# 1-Schematic_Lora.net
KiCad netlist of a schematic drawn in EasyEDA
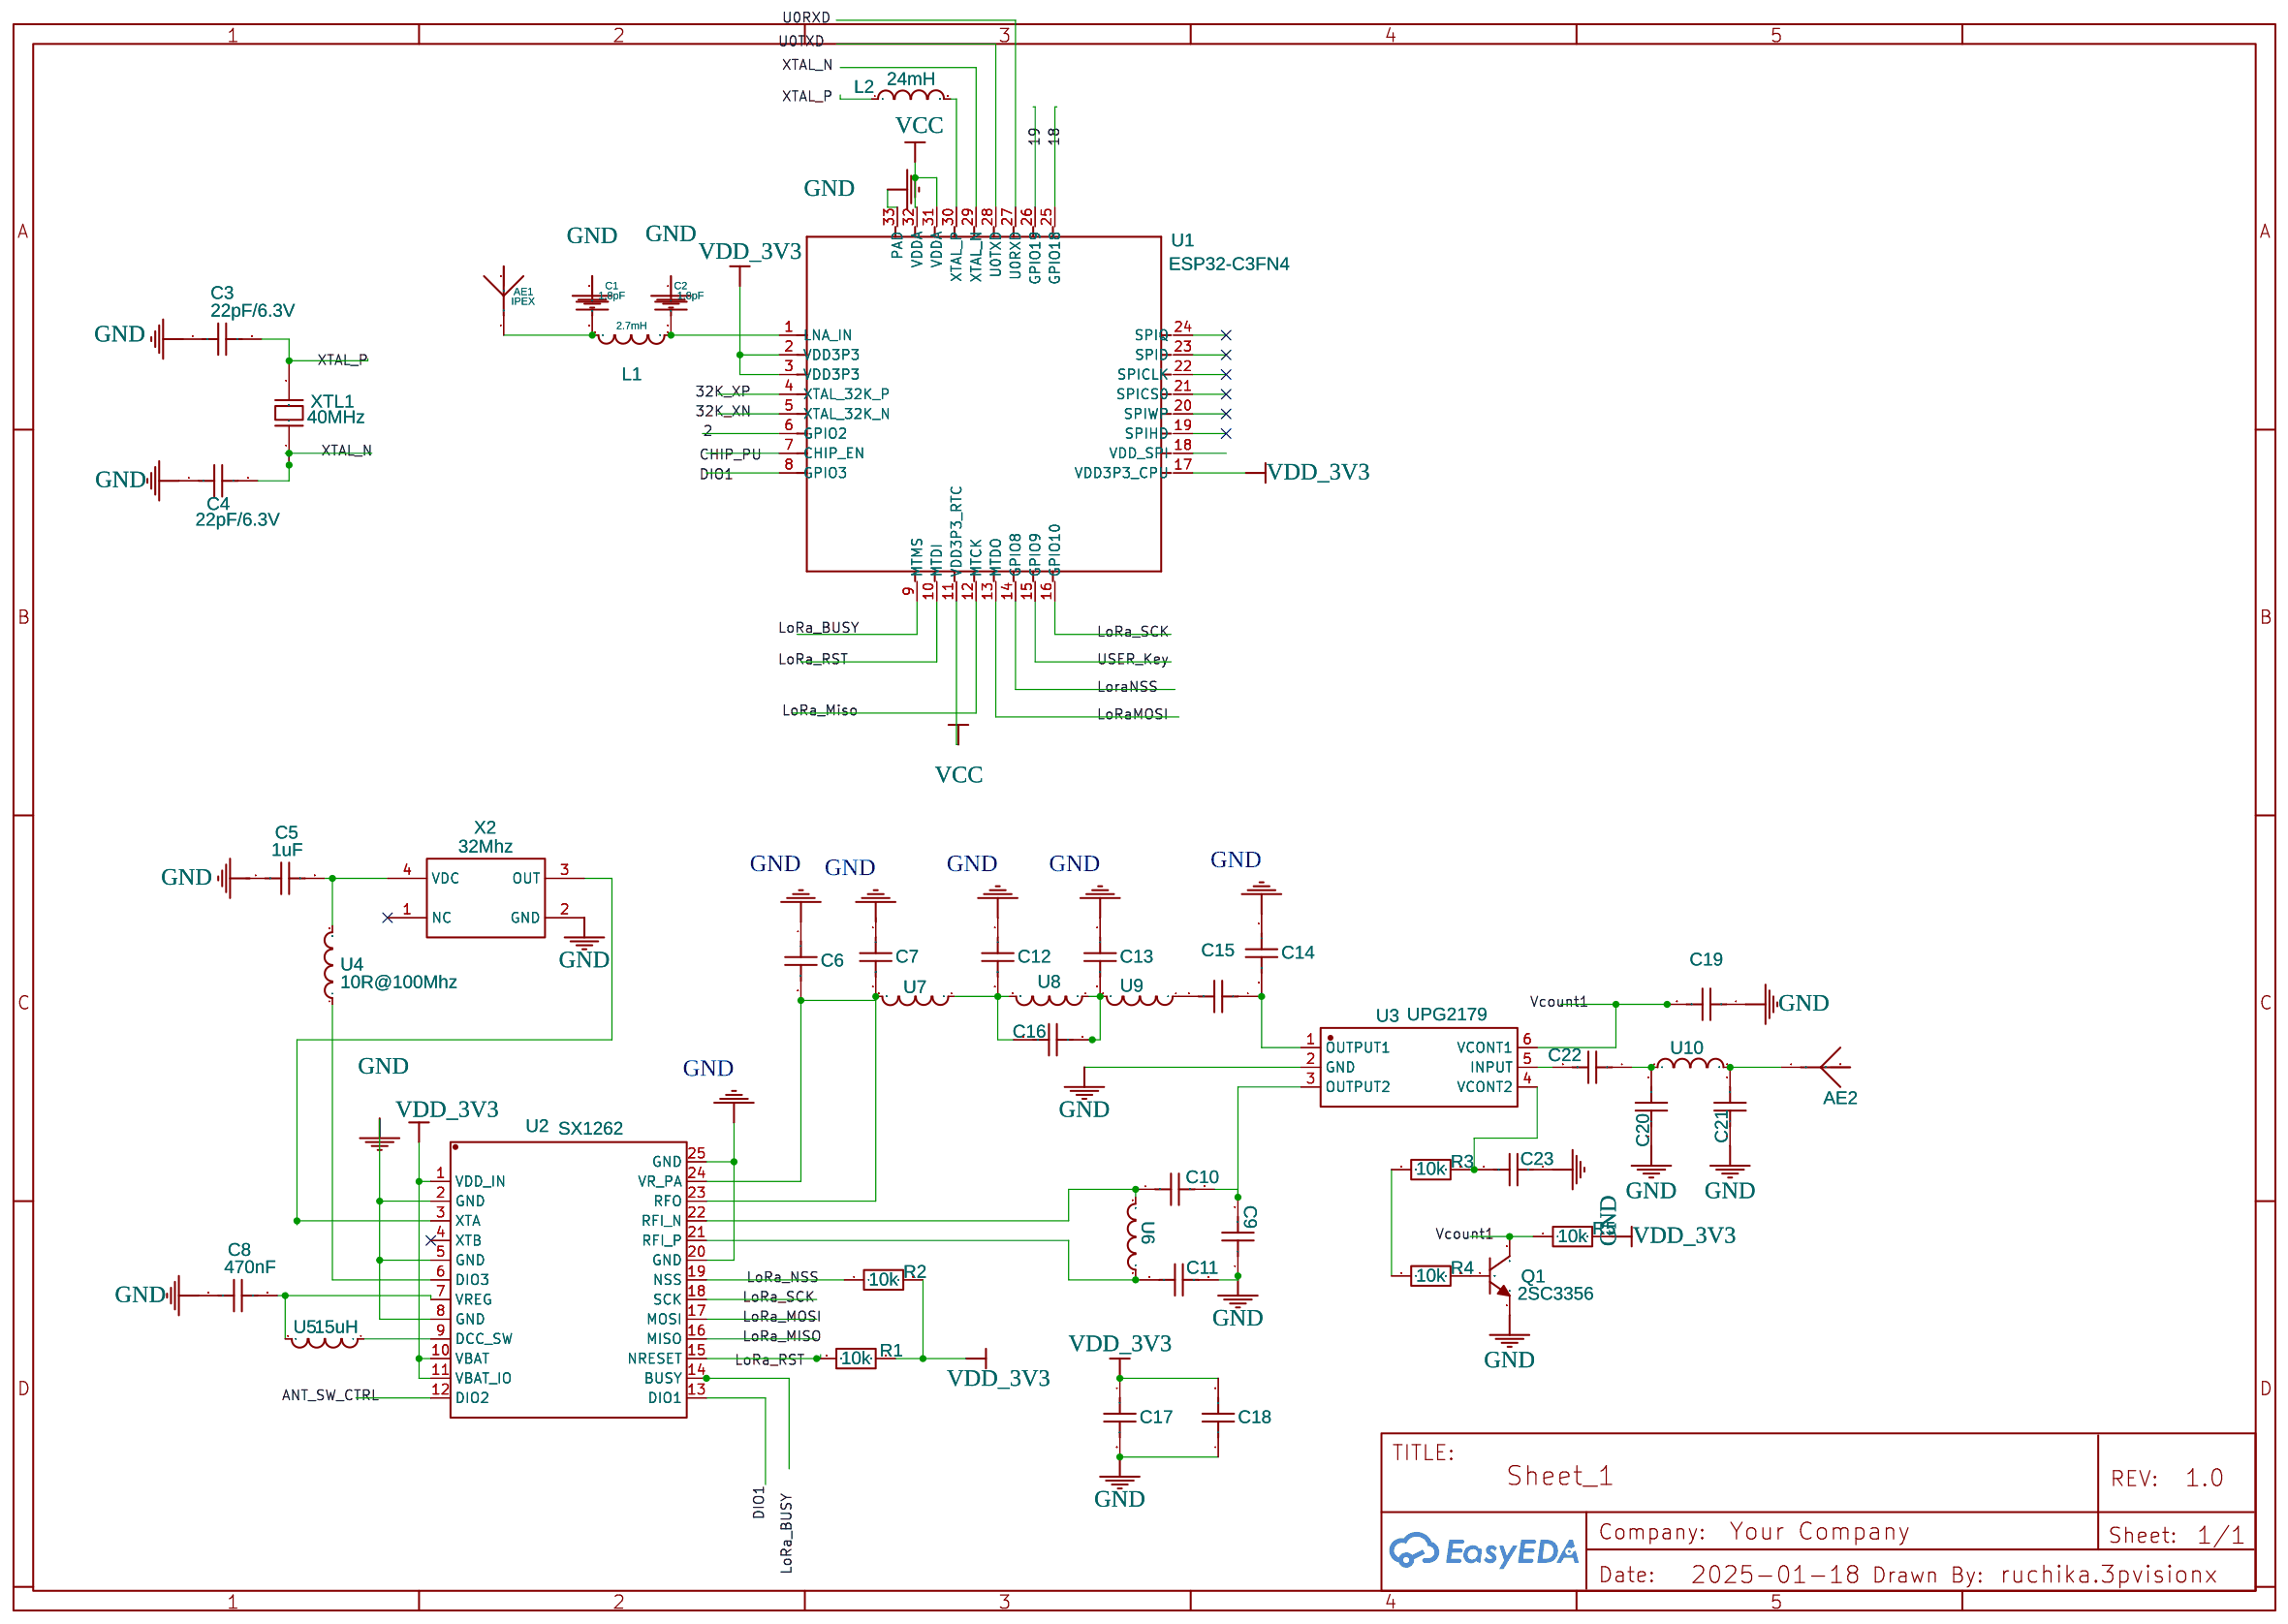
[diagram p0: schematic sheet]

(export (version "E")
  (design (tool "Eeschema 10.0.6"))
  (components
    (comp (ref "AE1")
      (value "IPEX")
      (fields
        (field (name "Manufacturer Part") "2450AT18A100E")
        (field (name "Manufacturer") "JOHANSON(约翰逊)")
      )
      (libsource (lib "") (part "2450AT18A100E"))
    )
    (comp (ref "AE2")
      (value "2450AT18A100E")
      (fields (field (name "Manufacturer") "JOHANSON(约翰逊)"))
      (libsource (lib "") (part "2450AT18A100E_1"))
    )
    (comp (ref "C1")
      (value "1.8pF")
      (fields
        (field (name "Manufacturer Part") "GJM1555C1H1R8BB01D")
        (field (name "Manufacturer") "muRata(村田)")
      )
      (libsource (lib "") (part "GJM1555C1H1R8BB01D"))
    )
    (comp (ref "C2")
      (value "1.8pF")
      (fields
        (field (name "Manufacturer Part") "GJM1555C1H1R8BB01D")
        (field (name "Manufacturer") "muRata(村田)")
      )
      (libsource (lib "") (part "GJM1555C1H1R8BB01D"))
    )
    (comp (ref "C3")
      (value "22pF/6.3V")
      (fields (field (name "Manufacturer Part") "22pF/6.3V(10%)-0402"))
      (libsource (lib "") (part "22PF/6.3V(10%)-0402"))
    )
    (comp (ref "C4")
      (value "22pF/6.3V")
      (fields (field (name "Manufacturer Part") "22pF/6.3V(10%)-0402"))
      (libsource (lib "") (part "22PF/6.3V(10%)-0402"))
    )
    (comp (ref "C5")
      (value "1uF")
      (fields
        (field (name "Manufacturer Part") "1uf/250V/CBBCapacitor")
        (field (name "Manufacturer") "ReliaPro")
      )
      (libsource (lib "") (part "1uf/250V/CBBCapacitor_2"))
    )
    (comp (ref "C6")
      (value "1uF")
      (fields
        (field (name "Manufacturer Part") "1uf/250V/CBBCapacitor")
        (field (name "Manufacturer") "ReliaPro")
      )
      (libsource (lib "") (part "1uf/250V/CBBCapacitor_1"))
    )
    (comp (ref "C7")
      (value "1uF")
      (fields
        (field (name "Manufacturer Part") "1uf/250V/CBBCapacitor")
        (field (name "Manufacturer") "ReliaPro")
      )
      (libsource (lib "") (part "1uf/250V/CBBCapacitor_1"))
    )
    (comp (ref "C8")
      (value "470nF")
      (fields
        (field (name "Manufacturer Part") "1uf/250V/CBBCapacitor")
        (field (name "Manufacturer") "ReliaPro")
      )
      (libsource (lib "") (part "1uf/250V/CBBCapacitor_2"))
    )
    (comp (ref "C9")
      (value "1uF")
      (fields
        (field (name "Manufacturer Part") "1uf/250V/CBBCapacitor")
        (field (name "Manufacturer") "ReliaPro")
      )
      (libsource (lib "") (part "1uf/250V/CBBCapacitor"))
    )
    (comp (ref "C10")
      (value "1uF")
      (fields
        (field (name "Manufacturer Part") "1uf/250V/CBBCapacitor")
        (field (name "Manufacturer") "ReliaPro")
      )
      (libsource (lib "") (part "1uf/250V/CBBCapacitor_2"))
    )
    (comp (ref "C11")
      (value "1uF")
      (fields
        (field (name "Manufacturer Part") "1uf/250V/CBBCapacitor")
        (field (name "Manufacturer") "ReliaPro")
      )
      (libsource (lib "") (part "1uf/250V/CBBCapacitor_2"))
    )
    (comp (ref "C12")
      (value "1uF")
      (fields
        (field (name "Manufacturer Part") "1uf/250V/CBBCapacitor")
        (field (name "Manufacturer") "ReliaPro")
      )
      (libsource (lib "") (part "1uf/250V/CBBCapacitor_1"))
    )
    (comp (ref "C13")
      (value "1uF")
      (fields
        (field (name "Manufacturer Part") "1uf/250V/CBBCapacitor")
        (field (name "Manufacturer") "ReliaPro")
      )
      (libsource (lib "") (part "1uf/250V/CBBCapacitor_1"))
    )
    (comp (ref "C14")
      (value "1uF")
      (fields
        (field (name "Manufacturer Part") "1uf/250V/CBBCapacitor")
        (field (name "Manufacturer") "ReliaPro")
      )
      (libsource (lib "") (part "1uf/250V/CBBCapacitor_1"))
    )
    (comp (ref "C15")
      (value "1uF")
      (fields
        (field (name "Manufacturer Part") "1uf/250V/CBBCapacitor")
        (field (name "Manufacturer") "ReliaPro")
      )
      (libsource (lib "") (part "1uf/250V/CBBCapacitor_3"))
    )
    (comp (ref "C16")
      (value "1uF")
      (fields
        (field (name "Manufacturer Part") "1uf/250V/CBBCapacitor")
        (field (name "Manufacturer") "ReliaPro")
      )
      (libsource (lib "") (part "1uf/250V/CBBCapacitor_3"))
    )
    (comp (ref "C17")
      (value "1uF")
      (fields
        (field (name "Manufacturer Part") "1uf/250V/CBBCapacitor")
        (field (name "Manufacturer") "ReliaPro")
      )
      (libsource (lib "") (part "1uf/250V/CBBCapacitor_1"))
    )
    (comp (ref "C18")
      (value "1uF")
      (fields
        (field (name "Manufacturer Part") "1uf/250V/CBBCapacitor")
        (field (name "Manufacturer") "ReliaPro")
      )
      (libsource (lib "") (part "1uf/250V/CBBCapacitor"))
    )
    (comp (ref "C19")
      (value "1uF")
      (fields
        (field (name "Manufacturer Part") "1uf/250V/CBBCapacitor")
        (field (name "Manufacturer") "ReliaPro")
      )
      (libsource (lib "") (part "1uf/250V/CBBCapacitor_3"))
    )
    (comp (ref "C20")
      (value "1uF")
      (fields
        (field (name "Manufacturer Part") "1uf/250V/CBBCapacitor")
        (field (name "Manufacturer") "ReliaPro")
      )
      (libsource (lib "") (part "1uf/250V/CBBCapacitor"))
    )
    (comp (ref "C21")
      (value "1uF")
      (fields
        (field (name "Manufacturer Part") "1uf/250V/CBBCapacitor")
        (field (name "Manufacturer") "ReliaPro")
      )
      (libsource (lib "") (part "1uf/250V/CBBCapacitor"))
    )
    (comp (ref "C22")
      (value "1uF")
      (fields
        (field (name "Manufacturer Part") "1uf/250V/CBBCapacitor")
        (field (name "Manufacturer") "ReliaPro")
      )
      (libsource (lib "") (part "1uf/250V/CBBCapacitor_3"))
    )
    (comp (ref "C23")
      (value "1uF")
      (fields
        (field (name "Manufacturer Part") "1uf/250V/CBBCapacitor")
        (field (name "Manufacturer") "ReliaPro")
      )
      (libsource (lib "") (part "1uf/250V/CBBCapacitor_3"))
    )
    (comp (ref "L1") (value "2.7mH") (libsource (lib "") (part "2.7mH sb3m")))
    (comp (ref "L2")
      (value "24mH")
      (fields (field (name "Manufacturer") "ML"))
      (libsource (lib "") (part "Inductor TH"))
    )
    (comp (ref "Q1")
      (value "2SC3356")
      (fields (field (name "Manufacturer") "FOSAN(富信)"))
      (libsource (lib "") (part "2SC3356_C5119709"))
    )
    (comp (ref "R1")
      (value "10k")
      (fields (field (name "Manufacturer Part") "贴片电阻ChipResistors"))
      (libsource (lib "") (part "贴片电阻CHIPRESISTORS"))
    )
    (comp (ref "R2")
      (value "10k")
      (fields (field (name "Manufacturer Part") "贴片电阻ChipResistors"))
      (libsource (lib "") (part "贴片电阻CHIPRESISTORS"))
    )
    (comp (ref "R3")
      (value "10k")
      (fields (field (name "Manufacturer Part") "贴片电阻ChipResistors"))
      (libsource (lib "") (part "贴片电阻CHIPRESISTORS"))
    )
    (comp (ref "R4")
      (value "10k")
      (fields (field (name "Manufacturer Part") "贴片电阻ChipResistors"))
      (libsource (lib "") (part "贴片电阻CHIPRESISTORS"))
    )
    (comp (ref "R5")
      (value "10k")
      (fields (field (name "Manufacturer Part") "贴片电阻ChipResistors"))
      (libsource (lib "") (part "贴片电阻CHIPRESISTORS"))
    )
    (comp (ref "U1") (value "ESP32-C3FN4") (libsource (lib "") (part "ESP32-C3FN4")))
    (comp (ref "U2")
      (value "SX1262")
      (fields (field (name "Manufacturer Part") "SX1262IMLTRT") (field (name "Manufacturer") "SEMTECH"))
      (libsource (lib "") (part "SX1262IMLTRT"))
    )
    (comp (ref "U3")
      (value "UPG2179")
      (fields
        (field (name "Manufacturer Part") "UPG2179TB-E4-A")
        (field (name "Manufacturer") "RENESAS(瑞萨)/IDT")
      )
      (libsource (lib "") (part "UPG2179TB-E4-A"))
    )
    (comp (ref "U4")
      (value "10R@100Mhz")
      (fields (field (name "Manufacturer Part") "10uH-INDUCTOR-0603"))
      (libsource (lib "") (part "10UH-INDUCTOR-0603_2"))
    )
    (comp (ref "U5")
      (value "15uH")
      (fields (field (name "Manufacturer Part") "10uH-INDUCTOR-0603"))
      (libsource (lib "") (part "10UH-INDUCTOR-0603_1"))
    )
    (comp (ref "U6")
      (value "15uH")
      (fields (field (name "Manufacturer Part") "10uH-INDUCTOR-0603"))
      (libsource (lib "") (part "10UH-INDUCTOR-0603_3"))
    )
    (comp (ref "U7")
      (value "15uH")
      (fields (field (name "Manufacturer Part") "10uH-INDUCTOR-0603"))
      (libsource (lib "") (part "10UH-INDUCTOR-0603"))
    )
    (comp (ref "U8")
      (value "15uH")
      (fields (field (name "Manufacturer Part") "10uH-INDUCTOR-0603"))
      (libsource (lib "") (part "10UH-INDUCTOR-0603"))
    )
    (comp (ref "U9")
      (value "15uH")
      (fields (field (name "Manufacturer Part") "10uH-INDUCTOR-0603"))
      (libsource (lib "") (part "10UH-INDUCTOR-0603_4"))
    )
    (comp (ref "U10")
      (value "15uH")
      (fields (field (name "Manufacturer Part") "10uH-INDUCTOR-0603"))
      (libsource (lib "") (part "10UH-INDUCTOR-0603_5"))
    )
    (comp (ref "X2")
      (value "32Mhz")
      (fields (field (name "Manufacturer") "YIC"))
      (libsource (lib "") (part "OSC40M-3.3/S5"))
    )
    (comp (ref "XTL1")
      (value "40MHz")
      (fields (field (name "Manufacturer Part") "NTPL INSIDE"))
      (libsource (lib "") (part "XTL - 16MHZ"))
    )
  )
  (nets
    (net (code "1") (name "/2") (class "Default")
      (node (ref "U1") (pin "6") (pinfunction "GPIO2_6") (pintype "unspecified"))
    )
    (net (code "9") (name "/LoRaMOSI") (class "Default")
      (node (ref "U1") (pin "13") (pinfunction "MTDO_13") (pintype "unspecified"))
    )
    (net (code "11") (name "/LoRa_MISO") (class "Default")
      (node (ref "U2") (pin "16") (pinfunction "MISO_16") (pintype "unspecified"))
    )
    (net (code "12") (name "/LoRa_MOSI") (class "Default")
      (node (ref "U2") (pin "17") (pinfunction "MOSI_17") (pintype "unspecified"))
    )
    (net (code "14") (name "/LoRa_NSS") (class "Default")
      (node (ref "R2") (pin "1") (pinfunction "1_1") (pintype "unspecified"))
      (node (ref "U2") (pin "19") (pinfunction "NSS_19") (pintype "unspecified"))
    )
    (net (code "16") (name "/LoRa_SCK") (class "Default")
      (node (ref "U1") (pin "16") (pinfunction "GPIO10_16") (pintype "unspecified"))
      (node (ref "U2") (pin "18") (pinfunction "SCK_18") (pintype "unspecified"))
    )
    (net (code "17") (name "/LoraNSS") (class "Default")
      (node (ref "U1") (pin "14") (pinfunction "GPIO8_14") (pintype "unspecified"))
    )
    (net (code "20") (name "/USER_Key") (class "Default")
      (node (ref "U1") (pin "15") (pinfunction "GPIO9_15") (pintype "unspecified"))
    )
    (net (code "22") (name "/XTAL_N") (class "Default")
      (node (ref "C4") (pin "2") (pinfunction "2_2") (pintype "unspecified"))
      (node (ref "XTL1") (pin "1") (pinfunction "1_1") (pintype "unspecified"))
    )
    (net (code "24") (name "GND") (class "Default")
      (node (ref "C1") (pin "1") (pinfunction "1_1") (pintype "input"))
      (node (ref "C11") (pin "2") (pinfunction "2_2") (pintype "unspecified"))
      (node (ref "C12") (pin "1") (pinfunction "1_1") (pintype "unspecified"))
      (node (ref "C13") (pin "1") (pinfunction "1_1") (pintype "unspecified"))
      (node (ref "C14") (pin "1") (pinfunction "1_1") (pintype "unspecified"))
      (node (ref "C17") (pin "2") (pinfunction "2_2") (pintype "unspecified"))
      (node (ref "C18") (pin "1") (pinfunction "1_1") (pintype "unspecified"))
      (node (ref "C19") (pin "1") (pinfunction "1_1") (pintype "unspecified"))
      (node (ref "C2") (pin "1") (pinfunction "1_1") (pintype "input"))
      (node (ref "C20") (pin "1") (pinfunction "1_1") (pintype "unspecified"))
      (node (ref "C21") (pin "1") (pinfunction "1_1") (pintype "unspecified"))
      (node (ref "C23") (pin "1") (pinfunction "1_1") (pintype "unspecified"))
      (node (ref "C3") (pin "1") (pinfunction "1_1") (pintype "unspecified"))
      (node (ref "C4") (pin "1") (pinfunction "1_1") (pintype "unspecified"))
      (node (ref "C6") (pin "1") (pinfunction "1_1") (pintype "unspecified"))
      (node (ref "C8") (pin "1") (pinfunction "1_1") (pintype "unspecified"))
      (node (ref "C9") (pin "1") (pinfunction "1_1") (pintype "unspecified"))
      (node (ref "Q1") (pin "1") (pinfunction "E_1") (pintype "input"))
      (node (ref "U1") (pin "33") (pinfunction "PAD_33") (pintype "unspecified"))
      (node (ref "U2") (pin "2") (pinfunction "GND_2") (pintype "unspecified"))
      (node (ref "U2") (pin "20") (pinfunction "GND_20") (pintype "unspecified"))
      (node (ref "U2") (pin "25") (pinfunction "GND_25") (pintype "unspecified"))
      (node (ref "U2") (pin "5") (pinfunction "GND_5") (pintype "unspecified"))
      (node (ref "U2") (pin "8") (pinfunction "GND_8") (pintype "unspecified"))
      (node (ref "U3") (pin "2") (pinfunction "GND_2") (pintype "unspecified"))
      (node (ref "X2") (pin "2") (pinfunction "GND_2") (pintype "unspecified"))
    )
    (net (code "25") (name "Net-(AE1-ANT)") (class "Default")
      (node (ref "AE1") (pin "1") (pinfunction "ANT_1") (pintype "unspecified"))
      (node (ref "C1") (pin "2") (pinfunction "2_2") (pintype "input"))
      (node (ref "L1") (pin "1") (pinfunction "1_1") (pintype "unspecified"))
    )
    (net (code "26") (name "Net-(AE2-ANT)") (class "Default")
      (node (ref "AE2") (pin "1") (pinfunction "ANT_1") (pintype "unspecified"))
      (node (ref "C21") (pin "2") (pinfunction "2_2") (pintype "unspecified"))
      (node (ref "U10") (pin "2") (pinfunction "2_2") (pintype "unspecified"))
    )
    (net (code "27") (name "Net-(C3-Pad2)") (class "Default")
      (node (ref "C3") (pin "2") (pinfunction "2_2") (pintype "unspecified"))
      (node (ref "XTL1") (pin "2") (pinfunction "2_2") (pintype "unspecified"))
    )
    (net (code "28") (name "Net-(C12-Pad2)") (class "Default")
      (node (ref "C12") (pin "2") (pinfunction "2_2") (pintype "unspecified"))
      (node (ref "C16") (pin "2") (pinfunction "2_2") (pintype "unspecified"))
      (node (ref "U7") (pin "1") (pinfunction "1_1") (pintype "unspecified"))
      (node (ref "U8") (pin "2") (pinfunction "2_2") (pintype "unspecified"))
    )
    (net (code "29") (name "Net-(C13-Pad2)") (class "Default")
      (node (ref "C13") (pin "2") (pinfunction "2_2") (pintype "unspecified"))
      (node (ref "C16") (pin "1") (pinfunction "1_1") (pintype "unspecified"))
      (node (ref "U8") (pin "1") (pinfunction "1_1") (pintype "unspecified"))
      (node (ref "U9") (pin "2") (pinfunction "2_2") (pintype "unspecified"))
    )
    (net (code "30") (name "Net-(C15-Pad2)") (class "Default")
      (node (ref "C15") (pin "2") (pinfunction "2_2") (pintype "unspecified"))
      (node (ref "U9") (pin "1") (pinfunction "1_1") (pintype "unspecified"))
    )
    (net (code "31") (name "Net-(C20-Pad2)") (class "Default")
      (node (ref "C20") (pin "2") (pinfunction "2_2") (pintype "unspecified"))
      (node (ref "C22") (pin "1") (pinfunction "1_1") (pintype "unspecified"))
      (node (ref "U10") (pin "1") (pinfunction "1_1") (pintype "unspecified"))
    )
    (net (code "32") (name "Net-(Q1-B)") (class "Default")
      (node (ref "Q1") (pin "2") (pinfunction "B_2") (pintype "input"))
      (node (ref "R4") (pin "2") (pinfunction "2_2") (pintype "unspecified"))
    )
    (net (code "33") (name "Net-(Q1-C)") (class "Default")
      (node (ref "Q1") (pin "3") (pinfunction "C_3") (pintype "input"))
      (node (ref "R5") (pin "1") (pinfunction "1_1") (pintype "unspecified"))
    )
    (net (code "34") (name "Net-(R3-Pad1)") (class "Default")
      (node (ref "R3") (pin "1") (pinfunction "1_1") (pintype "unspecified"))
      (node (ref "R4") (pin "1") (pinfunction "1_1") (pintype "unspecified"))
    )
    (net (code "35") (name "Net-(U1-LNA_IN)") (class "Default")
      (node (ref "C2") (pin "2") (pinfunction "2_2") (pintype "input"))
      (node (ref "L1") (pin "2") (pinfunction "2_2") (pintype "unspecified"))
      (node (ref "U1") (pin "1") (pinfunction "LNA_IN_1") (pintype "unspecified"))
    )
    (net (code "36") (name "Net-(U1-XTAL_P)") (class "Default")
      (node (ref "L2") (pin "2") (pinfunction "2_2") (pintype "unspecified"))
      (node (ref "U1") (pin "30") (pinfunction "XTAL_P_30") (pintype "unspecified"))
    )
    (net (code "37") (name "Net-(U2-DCC_SW)") (class "Default")
      (node (ref "U2") (pin "9") (pinfunction "DCC_SW_9") (pintype "unspecified"))
      (node (ref "U5") (pin "1") (pinfunction "1_1") (pintype "unspecified"))
    )
    (net (code "38") (name "Net-(U2-DIO3)") (class "Default")
      (node (ref "U2") (pin "6") (pinfunction "DIO3_6") (pintype "unspecified"))
      (node (ref "U4") (pin "1") (pinfunction "1_1") (pintype "unspecified"))
    )
    (net (code "39") (name "Net-(U2-NRESET)") (class "Default")
      (node (ref "R1") (pin "1") (pinfunction "1_1") (pintype "unspecified"))
      (node (ref "U2") (pin "15") (pinfunction "NRESET_15") (pintype "unspecified"))
    )
    (net (code "40") (name "Net-(U2-RFI_N)") (class "Default")
      (node (ref "C10") (pin "1") (pinfunction "1_1") (pintype "unspecified"))
      (node (ref "U2") (pin "22") (pinfunction "RFI_N_22") (pintype "unspecified"))
      (node (ref "U6") (pin "2") (pinfunction "2_2") (pintype "unspecified"))
    )
    (net (code "41") (name "Net-(U2-RFI_P)") (class "Default")
      (node (ref "C11") (pin "1") (pinfunction "1_1") (pintype "unspecified"))
      (node (ref "U2") (pin "21") (pinfunction "RFI_P_21") (pintype "unspecified"))
      (node (ref "U6") (pin "1") (pinfunction "1_1") (pintype "unspecified"))
    )
    (net (code "42") (name "Net-(U2-RFO)") (class "Default")
      (node (ref "C6") (pin "2") (pinfunction "2_2") (pintype "unspecified"))
      (node (ref "C7") (pin "2") (pinfunction "2_2") (pintype "unspecified"))
      (node (ref "U2") (pin "23") (pinfunction "RFO_23") (pintype "unspecified"))
      (node (ref "U2") (pin "24") (pinfunction "VR_PA_24") (pintype "unspecified"))
      (node (ref "U7") (pin "2") (pinfunction "2_2") (pintype "unspecified"))
    )
    (net (code "43") (name "Net-(U2-VREG)") (class "Default")
      (node (ref "C8") (pin "2") (pinfunction "2_2") (pintype "unspecified"))
      (node (ref "U2") (pin "7") (pinfunction "VREG_7") (pintype "unspecified"))
      (node (ref "U5") (pin "2") (pinfunction "2_2") (pintype "unspecified"))
    )
    (net (code "44") (name "Net-(U2-XTA)") (class "Default")
      (node (ref "U2") (pin "3") (pinfunction "XTA_3") (pintype "unspecified"))
      (node (ref "X2") (pin "3") (pinfunction "OUT_3") (pintype "unspecified"))
    )
    (net (code "45") (name "Net-(U3-INPUT)") (class "Default")
      (node (ref "C22") (pin "2") (pinfunction "2_2") (pintype "unspecified"))
      (node (ref "U3") (pin "5") (pinfunction "INPUT_5") (pintype "unspecified"))
    )
    (net (code "46") (name "Net-(U3-OUTPUT1)") (class "Default")
      (node (ref "C14") (pin "2") (pinfunction "2_2") (pintype "unspecified"))
      (node (ref "C15") (pin "1") (pinfunction "1_1") (pintype "unspecified"))
      (node (ref "U3") (pin "1") (pinfunction "OUTPUT1_1") (pintype "unspecified"))
    )
    (net (code "47") (name "Net-(U3-OUTPUT2)") (class "Default")
      (node (ref "C10") (pin "2") (pinfunction "2_2") (pintype "unspecified"))
      (node (ref "C9") (pin "2") (pinfunction "2_2") (pintype "unspecified"))
      (node (ref "U3") (pin "3") (pinfunction "OUTPUT2_3") (pintype "unspecified"))
    )
    (net (code "48") (name "Net-(U3-VCONT1)") (class "Default")
      (node (ref "C19") (pin "2") (pinfunction "2_2") (pintype "unspecified"))
      (node (ref "U3") (pin "6") (pinfunction "VCONT1_6") (pintype "unspecified"))
    )
    (net (code "49") (name "Net-(U3-VCONT2)") (class "Default")
      (node (ref "C23") (pin "2") (pinfunction "2_2") (pintype "unspecified"))
      (node (ref "R3") (pin "2") (pinfunction "2_2") (pintype "unspecified"))
      (node (ref "U3") (pin "4") (pinfunction "VCONT2_4") (pintype "unspecified"))
    )
    (net (code "50") (name "Net-(X2-VDC)") (class "Default")
      (node (ref "C5") (pin "2") (pinfunction "2_2") (pintype "unspecified"))
      (node (ref "U4") (pin "2") (pinfunction "2_2") (pintype "unspecified"))
      (node (ref "X2") (pin "4") (pinfunction "VDC_4") (pintype "unspecified"))
    )
    (net (code "51") (name "VCC") (class "Default")
      (node (ref "U1") (pin "11") (pinfunction "VDD3P3_RTC_11") (pintype "unspecified"))
      (node (ref "U1") (pin "31") (pinfunction "VDDA_31") (pintype "unspecified"))
      (node (ref "U1") (pin "32") (pinfunction "VDDA_32") (pintype "unspecified"))
    )
    (net (code "52") (name "VDD_3V3") (class "Default")
      (node (ref "C17") (pin "1") (pinfunction "1_1") (pintype "unspecified"))
      (node (ref "C18") (pin "2") (pinfunction "2_2") (pintype "unspecified"))
      (node (ref "R1") (pin "2") (pinfunction "2_2") (pintype "unspecified"))
      (node (ref "R2") (pin "2") (pinfunction "2_2") (pintype "unspecified"))
      (node (ref "R5") (pin "2") (pinfunction "2_2") (pintype "unspecified"))
      (node (ref "U1") (pin "17") (pinfunction "VDD3P3_CPU_17") (pintype "unspecified"))
      (node (ref "U1") (pin "2") (pinfunction "VDD3P3_2") (pintype "unspecified"))
      (node (ref "U1") (pin "3") (pinfunction "VDD3P3_3") (pintype "unspecified"))
      (node (ref "U2") (pin "1") (pinfunction "VDD_IN_1") (pintype "unspecified"))
      (node (ref "U2") (pin "10") (pinfunction "VBAT_10") (pintype "unspecified"))
      (node (ref "U2") (pin "11") (pinfunction "VBAT_IO_11") (pintype "unspecified"))
    )
    (net (code "53") (name "unconnected-(AE1-Pad2)") (class "Default")
      (node (ref "AE1") (pin "2") (pinfunction "2_2") (pintype "unspecified"))
    )
    (net (code "54") (name "unconnected-(AE2-Pad2)") (class "Default")
      (node (ref "AE2") (pin "2") (pinfunction "2_2") (pintype "unspecified"))
    )
    (net (code "55") (name "unconnected-(C5-Pad1)") (class "Default")
      (node (ref "C5") (pin "1") (pinfunction "1_1") (pintype "unspecified"))
    )
    (net (code "56") (name "unconnected-(C7-Pad1)") (class "Default")
      (node (ref "C7") (pin "1") (pinfunction "1_1") (pintype "unspecified"))
    )
    (net (code "57") (name "unconnected-(L2-Pad1)") (class "Default")
      (node (ref "L2") (pin "1") (pinfunction "1_1") (pintype "unspecified"))
    )
    (net (code "58") (name "unconnected-(U1-CHIP_EN-Pad7)") (class "Default")
      (node (ref "U1") (pin "7") (pinfunction "CHIP_EN_7") (pintype "unspecified"))
    )
    (net (code "59") (name "unconnected-(U1-GPIO3-Pad8)") (class "Default")
      (node (ref "U1") (pin "8") (pinfunction "GPIO3_8") (pintype "unspecified"))
    )
    (net (code "60") (name "unconnected-(U1-GPIO18-Pad25)") (class "Default")
      (node (ref "U1") (pin "25") (pinfunction "GPIO18_25") (pintype "unspecified"))
    )
    (net (code "61") (name "unconnected-(U1-GPIO19-Pad26)") (class "Default")
      (node (ref "U1") (pin "26") (pinfunction "GPIO19_26") (pintype "unspecified"))
    )
    (net (code "62") (name "unconnected-(U1-MTCK-Pad12)") (class "Default")
      (node (ref "U1") (pin "12") (pinfunction "MTCK_12") (pintype "unspecified"))
    )
    (net (code "63") (name "unconnected-(U1-MTDI-Pad10)") (class "Default")
      (node (ref "U1") (pin "10") (pinfunction "MTDI_10") (pintype "unspecified"))
    )
    (net (code "64") (name "unconnected-(U1-MTMS-Pad9)") (class "Default")
      (node (ref "U1") (pin "9") (pinfunction "MTMS_9") (pintype "unspecified"))
    )
    (net (code "65") (name "unconnected-(U1-SPICLK-Pad22)") (class "Default")
      (node (ref "U1") (pin "22") (pinfunction "SPICLK_22") (pintype "unspecified+no_connect"))
    )
    (net (code "66") (name "unconnected-(U1-SPICS0-Pad21)") (class "Default")
      (node (ref "U1") (pin "21") (pinfunction "SPICS0_21") (pintype "unspecified+no_connect"))
    )
    (net (code "67") (name "unconnected-(U1-SPID-Pad23)") (class "Default")
      (node (ref "U1") (pin "23") (pinfunction "SPID_23") (pintype "unspecified+no_connect"))
    )
    (net (code "68") (name "unconnected-(U1-SPIHD-Pad19)") (class "Default")
      (node (ref "U1") (pin "19") (pinfunction "SPIHD_19") (pintype "unspecified+no_connect"))
    )
    (net (code "69") (name "unconnected-(U1-SPIQ-Pad24)") (class "Default")
      (node (ref "U1") (pin "24") (pinfunction "SPIQ_24") (pintype "unspecified+no_connect"))
    )
    (net (code "70") (name "unconnected-(U1-SPIWP-Pad20)") (class "Default")
      (node (ref "U1") (pin "20") (pinfunction "SPIWP_20") (pintype "unspecified+no_connect"))
    )
    (net (code "71") (name "unconnected-(U1-U0RXD-Pad27)") (class "Default")
      (node (ref "U1") (pin "27") (pinfunction "U0RXD_27") (pintype "unspecified"))
    )
    (net (code "72") (name "unconnected-(U1-U0TXD-Pad28)") (class "Default")
      (node (ref "U1") (pin "28") (pinfunction "U0TXD_28") (pintype "unspecified"))
    )
    (net (code "73") (name "unconnected-(U1-VDD_SPI-Pad18)") (class "Default")
      (node (ref "U1") (pin "18") (pinfunction "VDD_SPI_18") (pintype "unspecified"))
    )
    (net (code "74") (name "unconnected-(U1-XTAL_32K_N-Pad5)") (class "Default")
      (node (ref "U1") (pin "5") (pinfunction "XTAL_32K_N_5") (pintype "unspecified"))
    )
    (net (code "75") (name "unconnected-(U1-XTAL_32K_P-Pad4)") (class "Default")
      (node (ref "U1") (pin "4") (pinfunction "XTAL_32K_P_4") (pintype "unspecified"))
    )
    (net (code "76") (name "unconnected-(U1-XTAL_N-Pad29)") (class "Default")
      (node (ref "U1") (pin "29") (pinfunction "XTAL_N_29") (pintype "unspecified"))
    )
    (net (code "77") (name "unconnected-(U2-BUSY-Pad14)") (class "Default")
      (node (ref "U2") (pin "14") (pinfunction "BUSY_14") (pintype "unspecified"))
    )
    (net (code "78") (name "unconnected-(U2-DIO1-Pad13)") (class "Default")
      (node (ref "U2") (pin "13") (pinfunction "DIO1_13") (pintype "unspecified"))
    )
    (net (code "79") (name "unconnected-(U2-DIO2-Pad12)") (class "Default")
      (node (ref "U2") (pin "12") (pinfunction "DIO2_12") (pintype "unspecified"))
    )
    (net (code "80") (name "unconnected-(U2-XTB-Pad4)") (class "Default")
      (node (ref "U2") (pin "4") (pinfunction "XTB_4") (pintype "unspecified+no_connect"))
    )
    (net (code "81") (name "unconnected-(X2-NC-Pad1)") (class "Default")
      (node (ref "X2") (pin "1") (pinfunction "NC_1") (pintype "unspecified+no_connect"))
    )
  )
)
